# STM32F103RCT6_MCU_LAB.net
KiCad netlist of a schematic drawn in Altium Designer
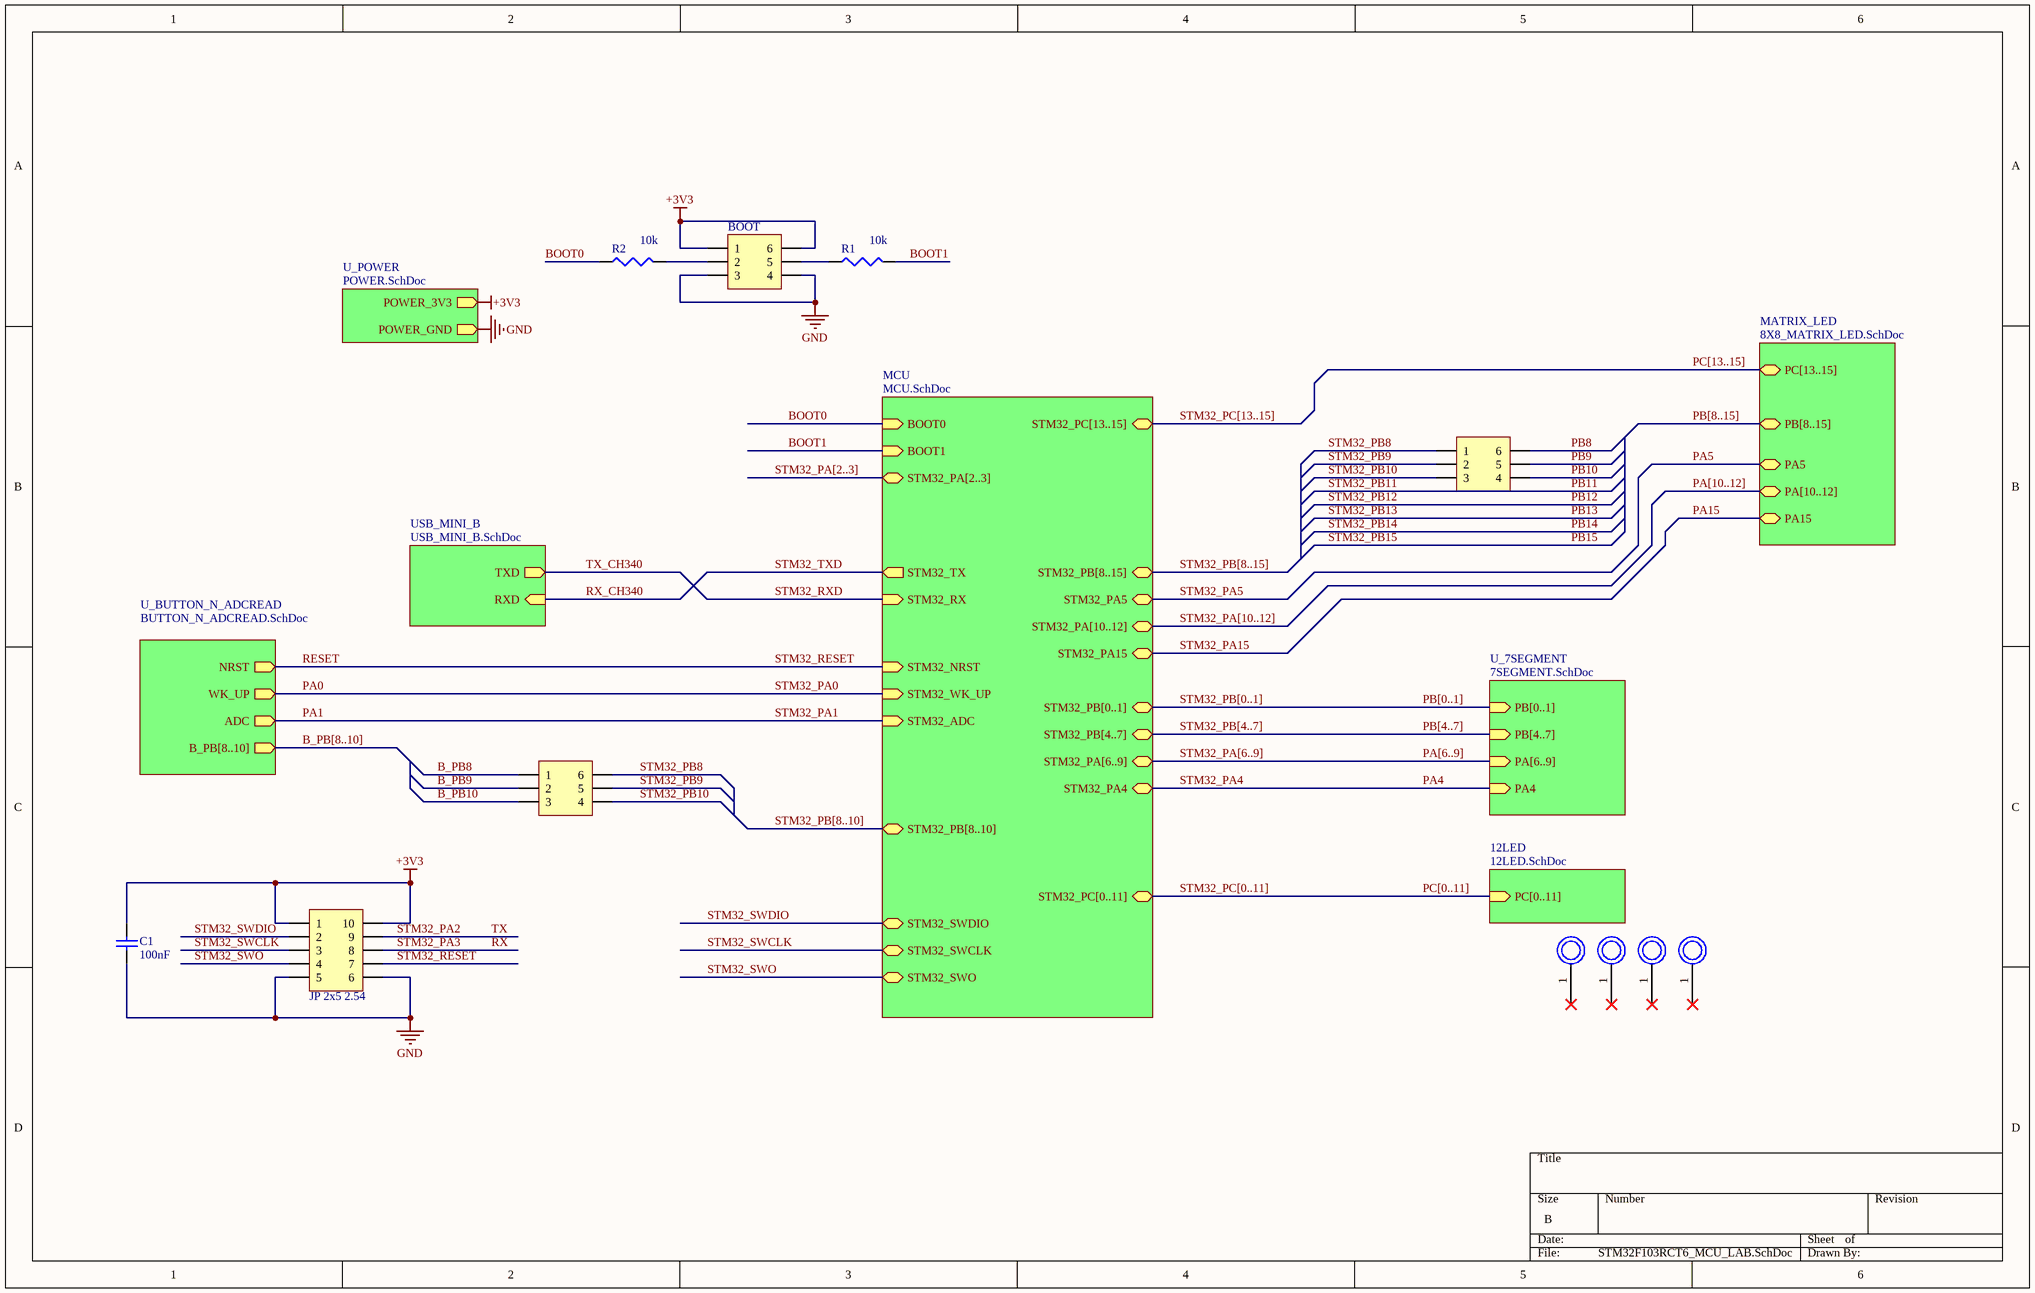
[diagram p0: STM32F103RCT6_MCU_LAB.SchDoc]

(export (version "E")
  (design (tool "Eeschema 10.0.6"))
  (components
    (comp (ref "BOOT")
      (value "JP 2x3 2.54")
      (footprint "JP 2x3 DT")
      (description "Cắm")
      (libsource (lib "Altium_Lib_by_KhueNguyenCreator") (part "JP 2x3 2.54 Duc Thang"))
    )
    (comp (ref "C1")
      (value "100nF")
      (footprint "CAPC0805(2012)145_L")
      (description "Chip Capacitor, 100nF +/-40%, 16V, 0805, Thickness 1.45 mm")
      (fields (field (name "TOLERANCE") "5%"))
      (libsource (lib "Ho Chi Minh City University of Technology") (part "CAP-NP-2"))
    )
    (comp (ref "HOLE_M1")
      (value "HOLE_M3")
      (footprint "HOLE M3")
      (libsource (lib "TRẦN HẢI THẢO QUẢNG") (part "HOLE_M3"))
    )
    (comp (ref "HOLE_M2")
      (value "HOLE_M3")
      (footprint "HOLE M3")
      (libsource (lib "TRẦN HẢI THẢO QUẢNG") (part "HOLE_M3"))
    )
    (comp (ref "HOLE_M3")
      (value "HOLE_M3")
      (footprint "HOLE M3")
      (libsource (lib "TRẦN HẢI THẢO QUẢNG") (part "HOLE_M3"))
    )
    (comp (ref "HOLE_M4")
      (value "HOLE_M3")
      (footprint "HOLE M3")
      (libsource (lib "TRẦN HẢI THẢO QUẢNG") (part "HOLE_M3"))
    )
    (comp (ref "JP1")
      (value "JP 2x3 2.54")
      (footprint "JP 2x3 DT")
      (description "Cắm")
      (libsource (lib "Altium_Lib_by_KhueNguyenCreator") (part "JP 2x3 2.54 Duc Thang"))
    )
    (comp (ref "JP2")
      (value "JP 2x5 2.54")
      (footprint "JP 2x5 DT")
      (description "Cắm")
      (libsource (lib "Altium_Lib_by_KhueNguyenCreator") (part "JP 2x5 2.54 Duc Thang"))
    )
    (comp (ref "JP3")
      (value "JP 2x3 2.54")
      (footprint "JP 2x3 DT")
      (description "Cắm")
      (libsource (lib "Altium_Lib_by_KhueNguyenCreator") (part "JP 2x3 2.54 Duc Thang"))
    )
    (comp (ref "R1")
      (value "10k")
      (footprint "0805 (2012 Metric)")
      (description "Oreki")
      (fields (field (name "Comment") "1k"))
      (libsource (lib "Ho Chi Minh City University of Technology") (part "RES-2"))
    )
    (comp (ref "R2")
      (value "10k")
      (footprint "0805 (2012 Metric)")
      (description "Oreki")
      (libsource (lib "Ho Chi Minh City University of Technology") (part "RES-2"))
    )
  )
  (nets
    (net (code "29") (name "+3V3") (class "Default")
      (node (ref "BOOT") (pin "1") (pinfunction "1_1") (pintype "passive"))
      (node (ref "BOOT") (pin "6") (pinfunction "6_6") (pintype "passive"))
      (node (ref "C1") (pin "2") (pinfunction "2_2") (pintype "passive"))
      (node (ref "JP2") (pin "1") (pinfunction "1_1") (pintype "passive"))
      (node (ref "JP2") (pin "10") (pinfunction "10_10") (pintype "passive"))
    )
    (net (code "30") (name "/BOOT0") (class "Default")
      (node (ref "R2") (pin "1") (pinfunction "1_1") (pintype "passive"))
    )
    (net (code "31") (name "/BOOT1") (class "Default")
      (node (ref "R1") (pin "2") (pinfunction "2_2") (pintype "passive"))
    )
    (net (code "32") (name "/B_PB8") (class "Default")
      (node (ref "JP3") (pin "1") (pinfunction "1_1") (pintype "passive"))
    )
    (net (code "33") (name "/B_PB9") (class "Default")
      (node (ref "JP3") (pin "2") (pinfunction "2_2") (pintype "passive"))
    )
    (net (code "34") (name "/B_PB10") (class "Default")
      (node (ref "JP3") (pin "3") (pinfunction "3_3") (pintype "passive"))
    )
    (net (code "43") (name "/PB8") (class "Default")
      (node (ref "JP1") (pin "6") (pinfunction "6_6") (pintype "passive"))
    )
    (net (code "44") (name "/PB9") (class "Default")
      (node (ref "JP1") (pin "5") (pinfunction "5_5") (pintype "passive"))
    )
    (net (code "45") (name "/PB10") (class "Default")
      (node (ref "JP1") (pin "4") (pinfunction "4_4") (pintype "passive"))
    )
    (net (code "56") (name "/RESET") (class "Default")
      (node (ref "JP2") (pin "7") (pinfunction "7_7") (pintype "passive"))
    )
    (net (code "58") (name "/STM32_PA2") (class "Default")
      (node (ref "JP2") (pin "9") (pinfunction "9_9") (pintype "passive"))
    )
    (net (code "59") (name "/STM32_PA3") (class "Default")
      (node (ref "JP2") (pin "8") (pinfunction "8_8") (pintype "passive"))
    )
    (net (code "61") (name "/STM32_PB8") (class "Default")
      (node (ref "JP1") (pin "1") (pinfunction "1_1") (pintype "passive"))
      (node (ref "JP3") (pin "6") (pinfunction "6_6") (pintype "passive"))
    )
    (net (code "62") (name "/STM32_PB9") (class "Default")
      (node (ref "JP1") (pin "2") (pinfunction "2_2") (pintype "passive"))
      (node (ref "JP3") (pin "5") (pinfunction "5_5") (pintype "passive"))
    )
    (net (code "63") (name "/STM32_PB10") (class "Default")
      (node (ref "JP1") (pin "3") (pinfunction "3_3") (pintype "passive"))
      (node (ref "JP3") (pin "4") (pinfunction "4_4") (pintype "passive"))
    )
    (net (code "67") (name "/STM32_SWCLK") (class "Default")
      (node (ref "JP2") (pin "3") (pinfunction "3_3") (pintype "passive"))
    )
    (net (code "68") (name "/STM32_SWDIO") (class "Default")
      (node (ref "JP2") (pin "2") (pinfunction "2_2") (pintype "passive"))
    )
    (net (code "69") (name "/STM32_SWO") (class "Default")
      (node (ref "JP2") (pin "4") (pinfunction "4_4") (pintype "passive"))
    )
    (net (code "70") (name "GND") (class "Default")
      (node (ref "BOOT") (pin "3") (pinfunction "3_3") (pintype "passive"))
      (node (ref "BOOT") (pin "4") (pinfunction "4_4") (pintype "passive"))
      (node (ref "C1") (pin "1") (pinfunction "1_1") (pintype "passive"))
      (node (ref "JP2") (pin "5") (pinfunction "5_5") (pintype "passive"))
      (node (ref "JP2") (pin "6") (pinfunction "6_6") (pintype "passive"))
    )
    (net (code "71") (name "Net-(BOOT-Pad2)") (class "Default")
      (node (ref "BOOT") (pin "2") (pinfunction "2_2") (pintype "passive"))
      (node (ref "R2") (pin "2") (pinfunction "2_2") (pintype "passive"))
    )
    (net (code "72") (name "Net-(BOOT-Pad5)") (class "Default")
      (node (ref "BOOT") (pin "5") (pinfunction "5_5") (pintype "passive"))
      (node (ref "R1") (pin "1") (pinfunction "1_1") (pintype "passive"))
    )
    (net (code "73") (name "unconnected-(HOLE_M1-Pad1)") (class "Default")
      (node (ref "HOLE_M1") (pin "1") (pinfunction "1_1") (pintype "passive+no_connect"))
    )
    (net (code "74") (name "unconnected-(HOLE_M2-Pad1)") (class "Default")
      (node (ref "HOLE_M2") (pin "1") (pinfunction "1_1") (pintype "passive+no_connect"))
    )
    (net (code "75") (name "unconnected-(HOLE_M3-Pad1)") (class "Default")
      (node (ref "HOLE_M3") (pin "1") (pinfunction "1_1") (pintype "passive+no_connect"))
    )
    (net (code "76") (name "unconnected-(HOLE_M4-Pad1)") (class "Default")
      (node (ref "HOLE_M4") (pin "1") (pinfunction "1_1") (pintype "passive+no_connect"))
    )
  )
)
